# vfddriver.net
KiCad netlist of a schematic drawn in EAGLE
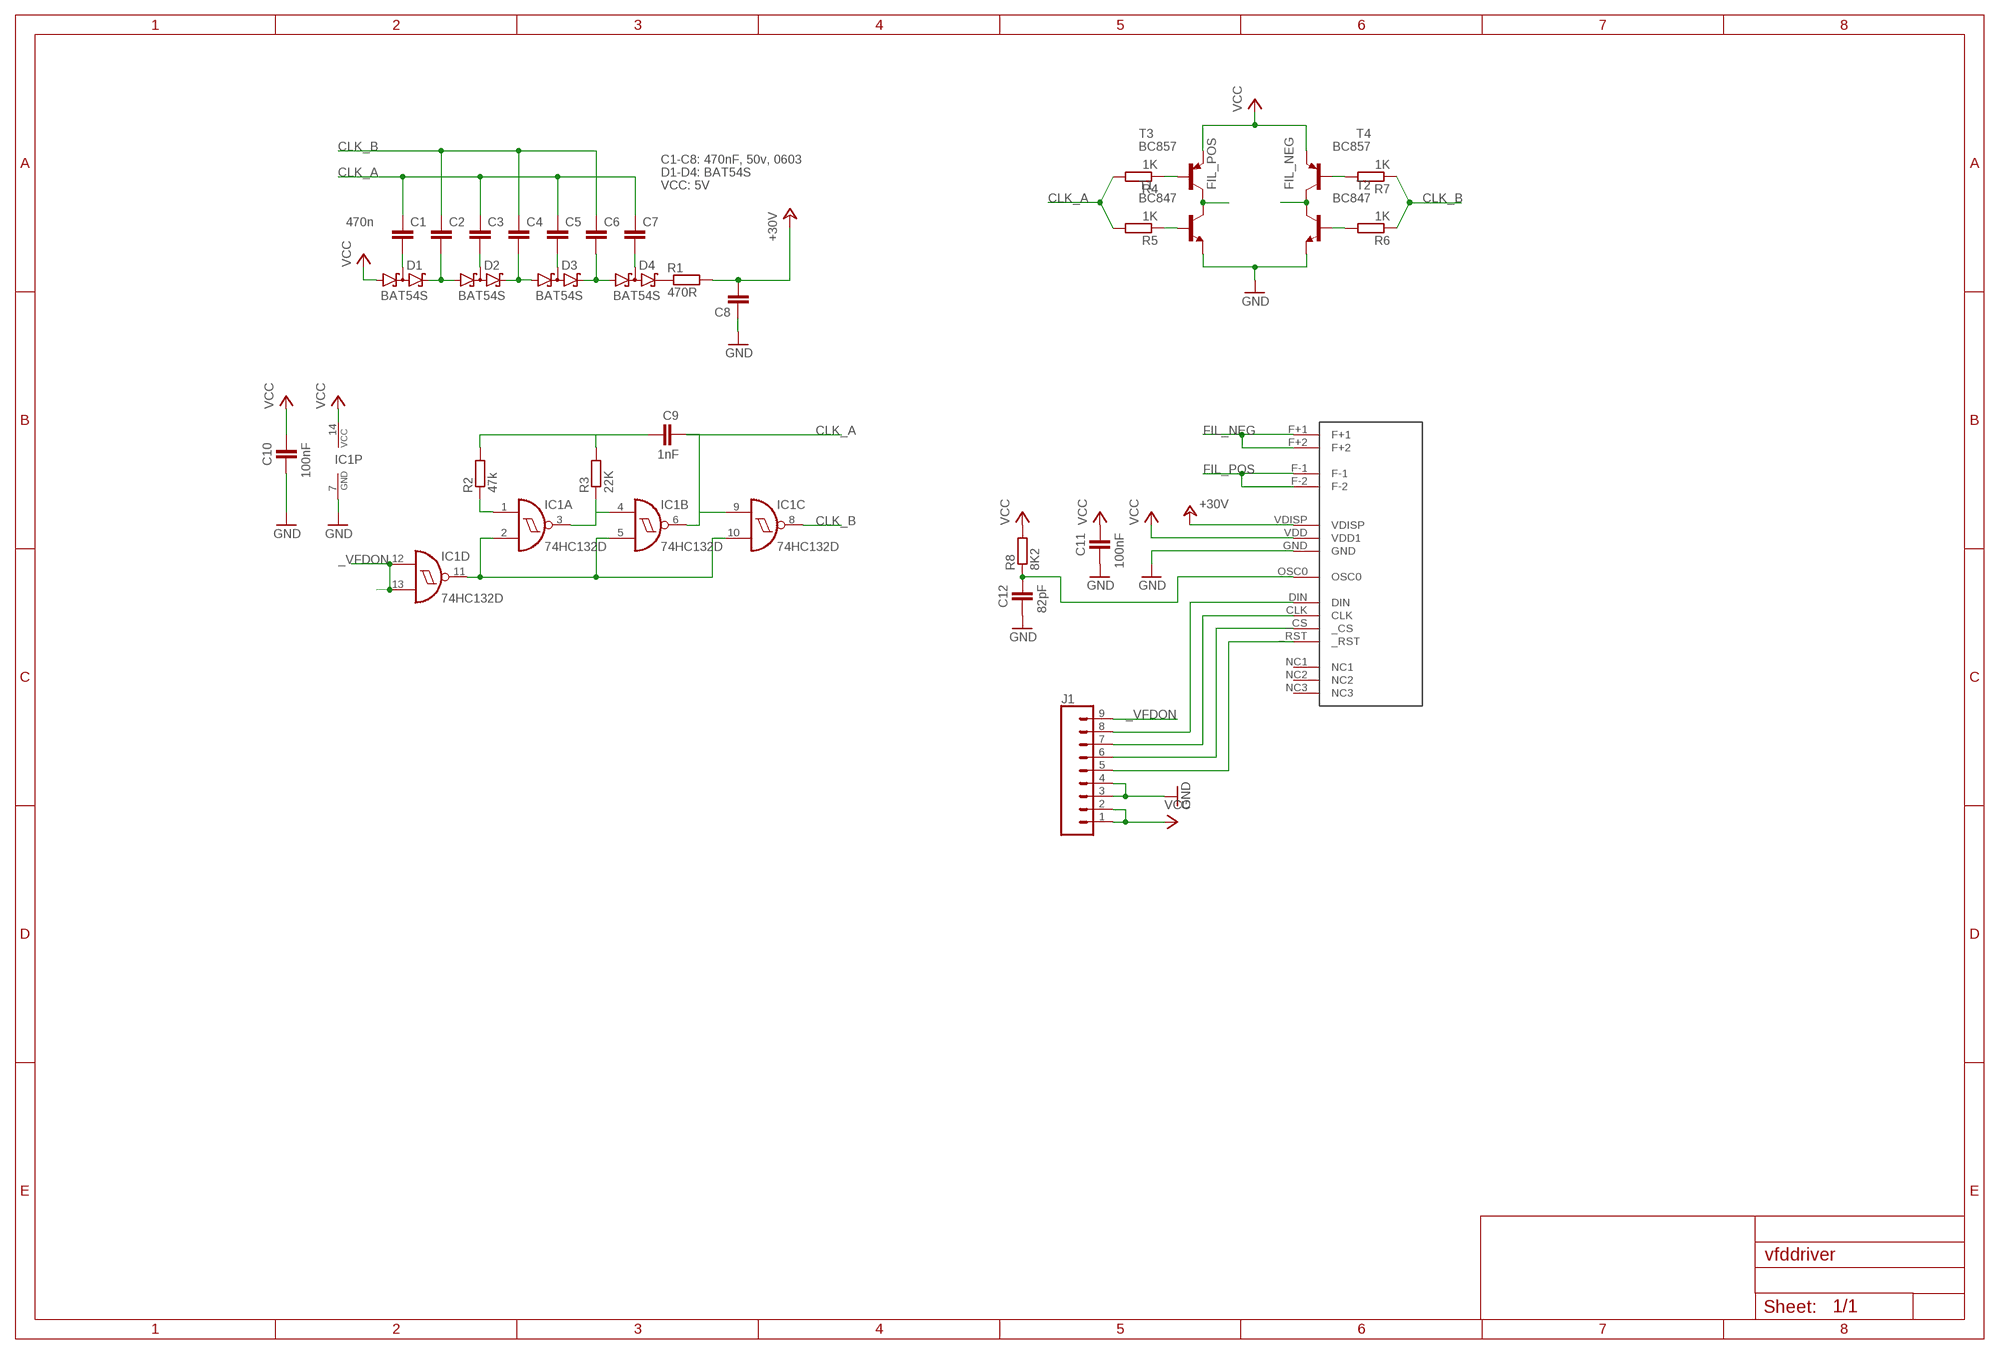
[diagram p0: schematic, sheet 1]

(export (version "E")
  (design (tool "Eeschema 10.0.6"))
  (components
    (comp (ref "C1")
      (value "470n")
      (footprint "eagle-import:C0603")
      (libsource (lib "eagle-import") (part "C-EUC0603"))
    )
    (comp (ref "C2")
      (value "470n 50v")
      (footprint "eagle-import:C0603")
      (libsource (lib "eagle-import") (part "C-EUC0603"))
    )
    (comp (ref "C3")
      (value "470n 50v")
      (footprint "eagle-import:C0603")
      (libsource (lib "eagle-import") (part "C-EUC0603"))
    )
    (comp (ref "C4")
      (value "470n 50v")
      (footprint "eagle-import:C0603")
      (libsource (lib "eagle-import") (part "C-EUC0603"))
    )
    (comp (ref "C5")
      (value "470n 50v")
      (footprint "eagle-import:C0603")
      (libsource (lib "eagle-import") (part "C-EUC0603"))
    )
    (comp (ref "C6")
      (value "470n")
      (footprint "eagle-import:C0603")
      (libsource (lib "eagle-import") (part "C-EUC0603"))
    )
    (comp (ref "C7")
      (value "470n 50v")
      (footprint "eagle-import:C0603")
      (libsource (lib "eagle-import") (part "C-EUC0603"))
    )
    (comp (ref "C8")
      (value "470n")
      (footprint "eagle-import:C0603")
      (libsource (lib "eagle-import") (part "C-EUC0603"))
    )
    (comp (ref "C9")
      (value "1nF")
      (footprint "eagle-import:C0603")
      (libsource (lib "eagle-import") (part "C-EUC0603"))
    )
    (comp (ref "C10")
      (value "100nF")
      (footprint "eagle-import:C0603")
      (libsource (lib "eagle-import") (part "C-EUC0603"))
    )
    (comp (ref "C11")
      (value "100nF")
      (footprint "eagle-import:C0603")
      (libsource (lib "eagle-import") (part "C-EUC0603"))
    )
    (comp (ref "C12")
      (value "82pF")
      (footprint "eagle-import:C0603")
      (libsource (lib "eagle-import") (part "C-EUC0603"))
    )
    (comp (ref "D1")
      (value "BAT54S")
      (footprint "eagle-import:SOT23")
      (libsource (lib "eagle-import") (part "BAT54S"))
    )
    (comp (ref "D2")
      (value "BAT54S")
      (footprint "eagle-import:SOT23")
      (libsource (lib "eagle-import") (part "BAT54S"))
    )
    (comp (ref "D3")
      (value "BAT54S")
      (footprint "eagle-import:SOT23")
      (libsource (lib "eagle-import") (part "BAT54S"))
    )
    (comp (ref "D4")
      (value "BAT54S")
      (footprint "eagle-import:SOT23")
      (libsource (lib "eagle-import") (part "BAT54S"))
    )
    (comp (ref "IC1")
      (value "74HC132D")
      (footprint "eagle-import:SO14")
      (libsource (lib "eagle-import") (part "74132DHC"))
    )
    (comp (ref "J1")
      (value "CONN_09LONGPADS")
      (footprint "eagle-import:1X09_LONGPADS")
      (libsource (lib "eagle-import") (part "CONN_09LONGPADS"))
    )
    (comp (ref "R1")
      (value "470R")
      (footprint "eagle-import:R0603")
      (libsource (lib "eagle-import") (part "R-EU_R0603"))
    )
    (comp (ref "R2")
      (value "47k")
      (footprint "eagle-import:R0603")
      (libsource (lib "eagle-import") (part "R-EU_R0603"))
    )
    (comp (ref "R3")
      (value "22K")
      (footprint "eagle-import:R0603")
      (libsource (lib "eagle-import") (part "R-EU_R0603"))
    )
    (comp (ref "R4")
      (value "1K")
      (footprint "eagle-import:R0603")
      (libsource (lib "eagle-import") (part "R-EU_R0603"))
    )
    (comp (ref "R5")
      (value "1K")
      (footprint "eagle-import:R0603")
      (libsource (lib "eagle-import") (part "R-EU_R0603"))
    )
    (comp (ref "R6")
      (value "1K")
      (footprint "eagle-import:R0603")
      (libsource (lib "eagle-import") (part "R-EU_R0603"))
    )
    (comp (ref "R7")
      (value "1K")
      (footprint "eagle-import:R0603")
      (libsource (lib "eagle-import") (part "R-EU_R0603"))
    )
    (comp (ref "R8")
      (value "8K2")
      (footprint "eagle-import:R0603")
      (libsource (lib "eagle-import") (part "R-EU_R0603"))
    )
    (comp (ref "T1")
      (value "BC847")
      (footprint "eagle-import:SOT23")
      (libsource (lib "eagle-import") (part "BC847"))
    )
    (comp (ref "T2")
      (value "BC847")
      (footprint "eagle-import:SOT23")
      (libsource (lib "eagle-import") (part "BC847"))
    )
    (comp (ref "T3")
      (value "BC857")
      (footprint "eagle-import:SOT23-BEC")
      (libsource (lib "eagle-import") (part "-PNP-SOT23-BECBC857A"))
    )
    (comp (ref "T4")
      (value "BC857")
      (footprint "eagle-import:SOT23-BEC")
      (libsource (lib "eagle-import") (part "-PNP-SOT23-BECBC857A"))
    )
    (comp (ref "U$1")
      (value "SAMSUNGHCS-12SS59T")
      (footprint "eagle-import:SAMSUNGHCS-12SS59T")
      (libsource (lib "eagle-import") (part "SAMSUNGHCS-12SS59T"))
    )
  )
  (nets
    (net (code "1") (name "+30V") (class "Default")
      (node (ref "C8") (pin "2") (pinfunction "2_2") (pintype "passive"))
      (node (ref "R1") (pin "2") (pinfunction "2_2") (pintype "passive"))
      (node (ref "U$1") (pin "VDISP") (pinfunction "VDISP_VDISP") (pintype "power_in"))
    )
    (net (code "2") (name "/CLK_A") (class "Default")
      (node (ref "C1") (pin "1") (pinfunction "1_1") (pintype "passive"))
      (node (ref "C3") (pin "1") (pinfunction "1_1") (pintype "passive"))
      (node (ref "C5") (pin "1") (pinfunction "1_1") (pintype "passive"))
      (node (ref "C7") (pin "1") (pinfunction "1_1") (pintype "passive"))
      (node (ref "C9") (pin "2") (pinfunction "2_2") (pintype "passive"))
      (node (ref "IC1") (pin "6") (pinfunction "O_6") (pintype "output"))
      (node (ref "IC1") (pin "9") (pinfunction "I0_9") (pintype "input"))
      (node (ref "R4") (pin "2") (pinfunction "2_2") (pintype "passive"))
      (node (ref "R5") (pin "2") (pinfunction "2_2") (pintype "passive"))
    )
    (net (code "3") (name "/CLK_B") (class "Default")
      (node (ref "C2") (pin "1") (pinfunction "1_1") (pintype "passive"))
      (node (ref "C4") (pin "1") (pinfunction "1_1") (pintype "passive"))
      (node (ref "C6") (pin "1") (pinfunction "1_1") (pintype "passive"))
      (node (ref "IC1") (pin "8") (pinfunction "O_8") (pintype "output"))
      (node (ref "R6") (pin "1") (pinfunction "1_1") (pintype "passive"))
      (node (ref "R7") (pin "1") (pinfunction "1_1") (pintype "passive"))
    )
    (net (code "4") (name "/FIL_NEG") (class "Default")
      (node (ref "T2") (pin "3") (pinfunction "C_3") (pintype "passive"))
      (node (ref "T4") (pin "C") (pinfunction "C_C") (pintype "passive"))
      (node (ref "U$1") (pin "F+1") (pinfunction "F+1_F+1") (pintype "power_in"))
      (node (ref "U$1") (pin "F+2") (pinfunction "F+2_F+2") (pintype "power_in"))
    )
    (net (code "5") (name "/FIL_POS") (class "Default")
      (node (ref "T1") (pin "3") (pinfunction "C_3") (pintype "passive"))
      (node (ref "T3") (pin "C") (pinfunction "C_C") (pintype "passive"))
      (node (ref "U$1") (pin "F-1") (pinfunction "F-1_F-1") (pintype "power_in"))
      (node (ref "U$1") (pin "F-2") (pinfunction "F-2_F-2") (pintype "power_in"))
    )
    (net (code "6") (name "/_VFDON") (class "Default")
      (node (ref "IC1") (pin "12") (pinfunction "I0_12") (pintype "input"))
      (node (ref "IC1") (pin "13") (pinfunction "I1_13") (pintype "input"))
      (node (ref "J1") (pin "9") (pinfunction "9_9") (pintype "passive"))
    )
    (net (code "7") (name "GND") (class "Default")
      (node (ref "C10") (pin "1") (pinfunction "1_1") (pintype "passive"))
      (node (ref "C11") (pin "1") (pinfunction "1_1") (pintype "passive"))
      (node (ref "C12") (pin "1") (pinfunction "1_1") (pintype "passive"))
      (node (ref "C8") (pin "1") (pinfunction "1_1") (pintype "passive"))
      (node (ref "IC1") (pin "7") (pinfunction "GND_7") (pintype "power_in"))
      (node (ref "J1") (pin "3") (pinfunction "3_3") (pintype "passive"))
      (node (ref "J1") (pin "4") (pinfunction "4_4") (pintype "passive"))
      (node (ref "T1") (pin "2") (pinfunction "E_2") (pintype "passive"))
      (node (ref "T2") (pin "2") (pinfunction "E_2") (pintype "passive"))
      (node (ref "U$1") (pin "GND") (pinfunction "GND_GND") (pintype "power_in"))
    )
    (net (code "8") (name "Net-(C9-Pad1)") (class "Default")
      (node (ref "C9") (pin "1") (pinfunction "1_1") (pintype "passive"))
      (node (ref "R2") (pin "2") (pinfunction "2_2") (pintype "passive"))
      (node (ref "R3") (pin "2") (pinfunction "2_2") (pintype "passive"))
    )
    (net (code "9") (name "Net-(C12-Pad2)") (class "Default")
      (node (ref "C12") (pin "2") (pinfunction "2_2") (pintype "passive"))
      (node (ref "R8") (pin "1") (pinfunction "1_1") (pintype "passive"))
      (node (ref "U$1") (pin "OSC0") (pinfunction "OSC0_OSC0") (pintype "bidirectional"))
    )
    (net (code "10") (name "Net-(D1-C1A2)") (class "Default")
      (node (ref "C1") (pin "2") (pinfunction "2_2") (pintype "passive"))
      (node (ref "D1") (pin "3") (pinfunction "C1A2_3") (pintype "passive"))
    )
    (net (code "11") (name "Net-(D1-C2)") (class "Default")
      (node (ref "C2") (pin "2") (pinfunction "2_2") (pintype "passive"))
      (node (ref "D1") (pin "2") (pinfunction "C2_2") (pintype "passive"))
      (node (ref "D2") (pin "1") (pinfunction "A1_1") (pintype "passive"))
    )
    (net (code "12") (name "Net-(D2-C1A2)") (class "Default")
      (node (ref "C3") (pin "2") (pinfunction "2_2") (pintype "passive"))
      (node (ref "D2") (pin "3") (pinfunction "C1A2_3") (pintype "passive"))
    )
    (net (code "13") (name "Net-(D2-C2)") (class "Default")
      (node (ref "C4") (pin "2") (pinfunction "2_2") (pintype "passive"))
      (node (ref "D2") (pin "2") (pinfunction "C2_2") (pintype "passive"))
      (node (ref "D3") (pin "1") (pinfunction "A1_1") (pintype "passive"))
    )
    (net (code "14") (name "Net-(D3-C1A2)") (class "Default")
      (node (ref "C5") (pin "2") (pinfunction "2_2") (pintype "passive"))
      (node (ref "D3") (pin "3") (pinfunction "C1A2_3") (pintype "passive"))
    )
    (net (code "15") (name "Net-(D3-C2)") (class "Default")
      (node (ref "C6") (pin "2") (pinfunction "2_2") (pintype "passive"))
      (node (ref "D3") (pin "2") (pinfunction "C2_2") (pintype "passive"))
      (node (ref "D4") (pin "1") (pinfunction "A1_1") (pintype "passive"))
    )
    (net (code "16") (name "Net-(D4-C1A2)") (class "Default")
      (node (ref "C7") (pin "2") (pinfunction "2_2") (pintype "passive"))
      (node (ref "D4") (pin "3") (pinfunction "C1A2_3") (pintype "passive"))
    )
    (net (code "17") (name "Net-(D4-C2)") (class "Default")
      (node (ref "D4") (pin "2") (pinfunction "C2_2") (pintype "passive"))
      (node (ref "R1") (pin "1") (pinfunction "1_1") (pintype "passive"))
    )
    (net (code "18") (name "Net-(IC1A-I0)") (class "Default")
      (node (ref "IC1") (pin "1") (pinfunction "I0_1") (pintype "input"))
      (node (ref "R2") (pin "1") (pinfunction "1_1") (pintype "passive"))
    )
    (net (code "19") (name "Net-(IC1A-I1)") (class "Default")
      (node (ref "IC1") (pin "10") (pinfunction "I1_10") (pintype "input"))
      (node (ref "IC1") (pin "11") (pinfunction "O_11") (pintype "output"))
      (node (ref "IC1") (pin "2") (pinfunction "I1_2") (pintype "input"))
      (node (ref "IC1") (pin "5") (pinfunction "I1_5") (pintype "input"))
    )
    (net (code "20") (name "Net-(IC1A-O)") (class "Default")
      (node (ref "IC1") (pin "3") (pinfunction "O_3") (pintype "output"))
      (node (ref "IC1") (pin "4") (pinfunction "I0_4") (pintype "input"))
      (node (ref "R3") (pin "1") (pinfunction "1_1") (pintype "passive"))
    )
    (net (code "21") (name "Net-(J1-Pad5)") (class "Default")
      (node (ref "J1") (pin "5") (pinfunction "5_5") (pintype "passive"))
      (node (ref "U$1") (pin "_RST") (pinfunction "_RST__RST") (pintype "bidirectional"))
    )
    (net (code "22") (name "Net-(J1-Pad6)") (class "Default")
      (node (ref "J1") (pin "6") (pinfunction "6_6") (pintype "passive"))
      (node (ref "U$1") (pin "_CS") (pinfunction "_CS__CS") (pintype "bidirectional"))
    )
    (net (code "23") (name "Net-(J1-Pad7)") (class "Default")
      (node (ref "J1") (pin "7") (pinfunction "7_7") (pintype "passive"))
      (node (ref "U$1") (pin "CLK") (pinfunction "CLK_CLK") (pintype "bidirectional"))
    )
    (net (code "24") (name "Net-(J1-Pad8)") (class "Default")
      (node (ref "J1") (pin "8") (pinfunction "8_8") (pintype "passive"))
      (node (ref "U$1") (pin "DIN") (pinfunction "DIN_DIN") (pintype "bidirectional"))
    )
    (net (code "25") (name "Net-(R4-Pad1)") (class "Default")
      (node (ref "R4") (pin "1") (pinfunction "1_1") (pintype "passive"))
      (node (ref "T3") (pin "B") (pinfunction "B_B") (pintype "passive"))
    )
    (net (code "26") (name "Net-(R7-Pad2)") (class "Default")
      (node (ref "R7") (pin "2") (pinfunction "2_2") (pintype "passive"))
      (node (ref "T4") (pin "B") (pinfunction "B_B") (pintype "passive"))
    )
    (net (code "27") (name "Net-(T1-B)") (class "Default")
      (node (ref "R5") (pin "1") (pinfunction "1_1") (pintype "passive"))
      (node (ref "T1") (pin "1") (pinfunction "B_1") (pintype "passive"))
    )
    (net (code "28") (name "Net-(T2-B)") (class "Default")
      (node (ref "R6") (pin "2") (pinfunction "2_2") (pintype "passive"))
      (node (ref "T2") (pin "1") (pinfunction "B_1") (pintype "passive"))
    )
    (net (code "29") (name "VCC") (class "Default")
      (node (ref "C10") (pin "2") (pinfunction "2_2") (pintype "passive"))
      (node (ref "C11") (pin "2") (pinfunction "2_2") (pintype "passive"))
      (node (ref "D1") (pin "1") (pinfunction "A1_1") (pintype "passive"))
      (node (ref "IC1") (pin "14") (pinfunction "VCC_14") (pintype "power_in"))
      (node (ref "J1") (pin "1") (pinfunction "1_1") (pintype "passive"))
      (node (ref "J1") (pin "2") (pinfunction "2_2") (pintype "passive"))
      (node (ref "R8") (pin "2") (pinfunction "2_2") (pintype "passive"))
      (node (ref "T3") (pin "E") (pinfunction "E_E") (pintype "passive"))
      (node (ref "T4") (pin "E") (pinfunction "E_E") (pintype "passive"))
      (node (ref "U$1") (pin "VDD") (pinfunction "VDD1_VDD") (pintype "power_in"))
    )
    (net (code "30") (name "unconnected-(U$1-PadNC1)") (class "Default")
      (node (ref "U$1") (pin "NC1") (pinfunction "NC1_NC1") (pintype "no_connect"))
    )
    (net (code "31") (name "unconnected-(U$1-PadNC2)") (class "Default")
      (node (ref "U$1") (pin "NC2") (pinfunction "NC2_NC2") (pintype "no_connect"))
    )
    (net (code "32") (name "unconnected-(U$1-PadNC3)") (class "Default")
      (node (ref "U$1") (pin "NC3") (pinfunction "NC3_NC3") (pintype "no_connect"))
    )
  )
)
